# 06_Switch.net
KiCad netlist of a schematic drawn in Altium Designer
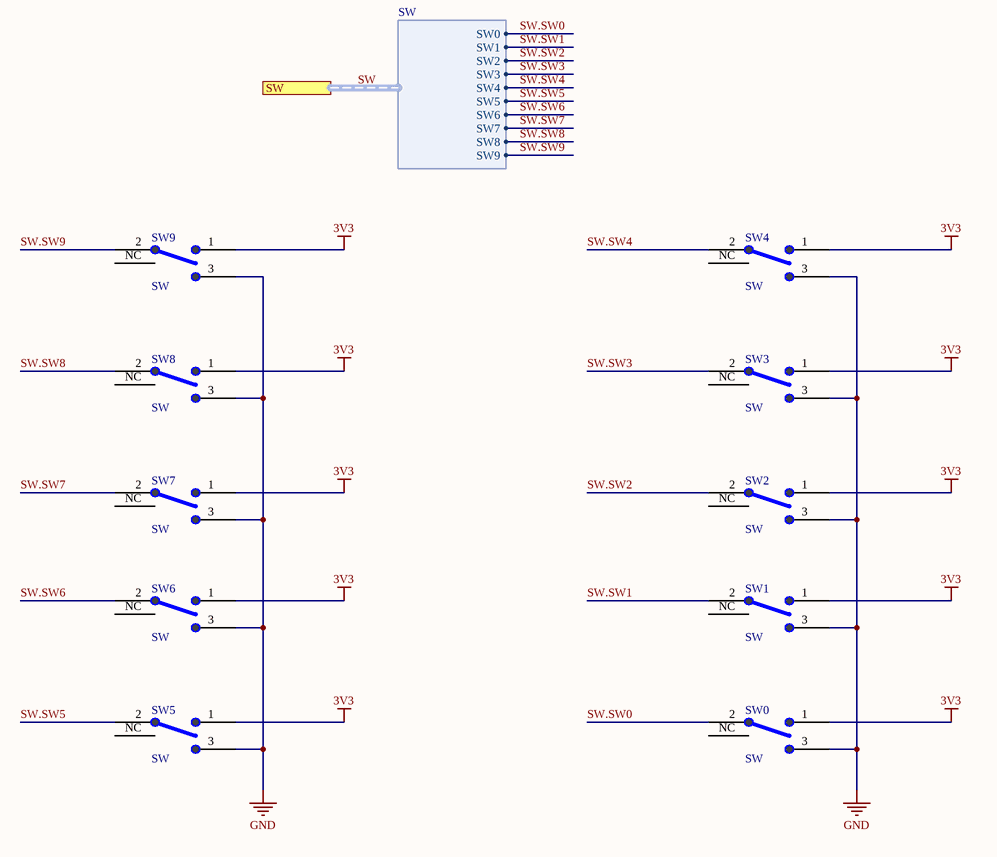
[diagram p0: 06_Switch.SchDoc]

(export (version "E")
  (design (tool "Eeschema 10.0.6"))
  (components
    (comp (ref "SW0")
      (value "SW")
      (footprint "SW_OS102011MS2Q")
      (description "OS102011MS2QN OS Series\r\nMiniature Slide Switches\r1-2 , 2-3 (on,on)")
      (libsource (lib "Quatro_SchLib") (part "SW"))
    )
    (comp (ref "SW1")
      (value "SW")
      (footprint "SW_OS102011MS2Q")
      (description "OS102011MS2QN OS Series\r\nMiniature Slide Switches\r1-2 , 2-3 (on,on)")
      (libsource (lib "Quatro_SchLib") (part "SW"))
    )
    (comp (ref "SW2")
      (value "SW")
      (footprint "SW_OS102011MS2Q")
      (description "OS102011MS2QN OS Series\r\nMiniature Slide Switches\r1-2 , 2-3 (on,on)")
      (libsource (lib "Quatro_SchLib") (part "SW"))
    )
    (comp (ref "SW3")
      (value "SW")
      (footprint "SW_OS102011MS2Q")
      (description "OS102011MS2QN OS Series\r\nMiniature Slide Switches\r1-2 , 2-3 (on,on)")
      (libsource (lib "Quatro_SchLib") (part "SW"))
    )
    (comp (ref "SW4")
      (value "SW")
      (footprint "SW_OS102011MS2Q")
      (description "OS102011MS2QN OS Series\r\nMiniature Slide Switches\r1-2 , 2-3 (on,on)")
      (libsource (lib "Quatro_SchLib") (part "SW"))
    )
    (comp (ref "SW5")
      (value "SW")
      (footprint "SW_OS102011MS2Q")
      (description "OS102011MS2QN OS Series\r\nMiniature Slide Switches\r1-2 , 2-3 (on,on)")
      (libsource (lib "Quatro_SchLib") (part "SW"))
    )
    (comp (ref "SW6")
      (value "SW")
      (footprint "SW_OS102011MS2Q")
      (description "OS102011MS2QN OS Series\r\nMiniature Slide Switches\r1-2 , 2-3 (on,on)")
      (libsource (lib "Quatro_SchLib") (part "SW"))
    )
    (comp (ref "SW7")
      (value "SW")
      (footprint "SW_OS102011MS2Q")
      (description "OS102011MS2QN OS Series\r\nMiniature Slide Switches\r1-2 , 2-3 (on,on)")
      (libsource (lib "Quatro_SchLib") (part "SW"))
    )
    (comp (ref "SW8")
      (value "SW")
      (footprint "SW_OS102011MS2Q")
      (description "OS102011MS2QN OS Series\r\nMiniature Slide Switches\r1-2 , 2-3 (on,on)")
      (libsource (lib "Quatro_SchLib") (part "SW"))
    )
    (comp (ref "SW9")
      (value "SW")
      (footprint "SW_OS102011MS2Q")
      (description "OS102011MS2QN OS Series\r\nMiniature Slide Switches\r1-2 , 2-3 (on,on)")
      (libsource (lib "Quatro_SchLib") (part "SW"))
    )
  )
  (nets
    (net (code "2") (name "/SW.SW0") (class "Default")
      (node (ref "SW0") (pin "2") (pinfunction "2_2") (pintype "passive"))
    )
    (net (code "3") (name "/SW.SW1") (class "Default")
      (node (ref "SW1") (pin "2") (pinfunction "2_2") (pintype "passive"))
    )
    (net (code "4") (name "/SW.SW2") (class "Default")
      (node (ref "SW2") (pin "2") (pinfunction "2_2") (pintype "passive"))
    )
    (net (code "5") (name "/SW.SW3") (class "Default")
      (node (ref "SW3") (pin "2") (pinfunction "2_2") (pintype "passive"))
    )
    (net (code "6") (name "/SW.SW4") (class "Default")
      (node (ref "SW4") (pin "2") (pinfunction "2_2") (pintype "passive"))
    )
    (net (code "7") (name "/SW.SW5") (class "Default")
      (node (ref "SW5") (pin "2") (pinfunction "2_2") (pintype "passive"))
    )
    (net (code "8") (name "/SW.SW6") (class "Default")
      (node (ref "SW6") (pin "2") (pinfunction "2_2") (pintype "passive"))
    )
    (net (code "9") (name "/SW.SW7") (class "Default")
      (node (ref "SW7") (pin "2") (pinfunction "2_2") (pintype "passive"))
    )
    (net (code "10") (name "/SW.SW8") (class "Default")
      (node (ref "SW8") (pin "2") (pinfunction "2_2") (pintype "passive"))
    )
    (net (code "11") (name "/SW.SW9") (class "Default")
      (node (ref "SW9") (pin "2") (pinfunction "2_2") (pintype "passive"))
    )
    (net (code "13") (name "3V3") (class "Default")
      (node (ref "SW0") (pin "1") (pinfunction "1_1") (pintype "passive"))
      (node (ref "SW1") (pin "1") (pinfunction "1_1") (pintype "passive"))
      (node (ref "SW2") (pin "1") (pinfunction "1_1") (pintype "passive"))
      (node (ref "SW3") (pin "1") (pinfunction "1_1") (pintype "passive"))
      (node (ref "SW4") (pin "1") (pinfunction "1_1") (pintype "passive"))
      (node (ref "SW5") (pin "1") (pinfunction "1_1") (pintype "passive"))
      (node (ref "SW6") (pin "1") (pinfunction "1_1") (pintype "passive"))
      (node (ref "SW7") (pin "1") (pinfunction "1_1") (pintype "passive"))
      (node (ref "SW8") (pin "1") (pinfunction "1_1") (pintype "passive"))
      (node (ref "SW9") (pin "1") (pinfunction "1_1") (pintype "passive"))
    )
    (net (code "14") (name "GND") (class "Default")
      (node (ref "SW0") (pin "3") (pinfunction "29_3") (pintype "passive"))
      (node (ref "SW1") (pin "3") (pinfunction "29_3") (pintype "passive"))
      (node (ref "SW2") (pin "3") (pinfunction "29_3") (pintype "passive"))
      (node (ref "SW3") (pin "3") (pinfunction "29_3") (pintype "passive"))
      (node (ref "SW4") (pin "3") (pinfunction "29_3") (pintype "passive"))
      (node (ref "SW5") (pin "3") (pinfunction "29_3") (pintype "passive"))
      (node (ref "SW6") (pin "3") (pinfunction "29_3") (pintype "passive"))
      (node (ref "SW7") (pin "3") (pinfunction "29_3") (pintype "passive"))
      (node (ref "SW8") (pin "3") (pinfunction "29_3") (pintype "passive"))
      (node (ref "SW9") (pin "3") (pinfunction "29_3") (pintype "passive"))
    )
    (net (code "15") (name "unconnected-(SW0-PadNC)") (class "Default")
      (node (ref "SW0") (pin "NC") (pinfunction "NC_NC") (pintype "passive"))
    )
    (net (code "16") (name "unconnected-(SW1-PadNC)") (class "Default")
      (node (ref "SW1") (pin "NC") (pinfunction "NC_NC") (pintype "passive"))
    )
    (net (code "17") (name "unconnected-(SW2-PadNC)") (class "Default")
      (node (ref "SW2") (pin "NC") (pinfunction "NC_NC") (pintype "passive"))
    )
    (net (code "18") (name "unconnected-(SW3-PadNC)") (class "Default")
      (node (ref "SW3") (pin "NC") (pinfunction "NC_NC") (pintype "passive"))
    )
    (net (code "19") (name "unconnected-(SW4-PadNC)") (class "Default")
      (node (ref "SW4") (pin "NC") (pinfunction "NC_NC") (pintype "passive"))
    )
    (net (code "20") (name "unconnected-(SW5-PadNC)") (class "Default")
      (node (ref "SW5") (pin "NC") (pinfunction "NC_NC") (pintype "passive"))
    )
    (net (code "21") (name "unconnected-(SW6-PadNC)") (class "Default")
      (node (ref "SW6") (pin "NC") (pinfunction "NC_NC") (pintype "passive"))
    )
    (net (code "22") (name "unconnected-(SW7-PadNC)") (class "Default")
      (node (ref "SW7") (pin "NC") (pinfunction "NC_NC") (pintype "passive"))
    )
    (net (code "23") (name "unconnected-(SW8-PadNC)") (class "Default")
      (node (ref "SW8") (pin "NC") (pinfunction "NC_NC") (pintype "passive"))
    )
    (net (code "24") (name "unconnected-(SW9-PadNC)") (class "Default")
      (node (ref "SW9") (pin "NC") (pinfunction "NC_NC") (pintype "passive"))
    )
  )
)
